# generic_RGB_LED_driver.net
KiCad netlist of a schematic drawn in EAGLE
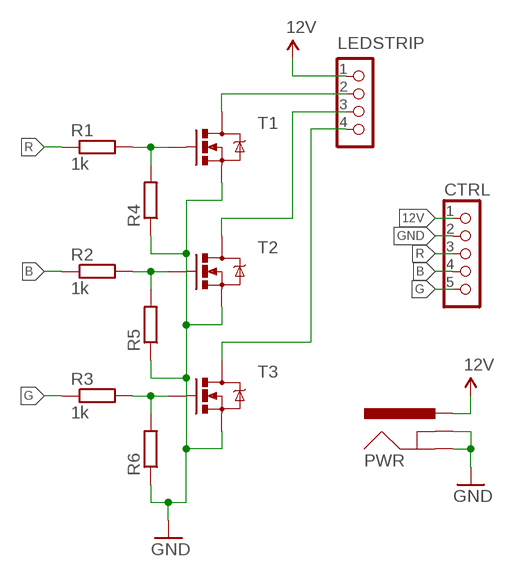
[diagram p0: schematic, sheet 1]

(export (version "E")
  (design (tool "Eeschema 10.0.6"))
  (components
    (comp (ref "CTRL")
      (value "CON_HEADER_1X05-PTH")
      (footprint "eagle-import:M1X5")
      (libsource (lib "eagle-import") (part "CON_HEADER_1X05-PTH"))
    )
    (comp (ref "LEDSTRIP")
      (value "12vBRG")
      (footprint "eagle-import:M1X4")
      (libsource (lib "eagle-import") (part "CON_HEADER_1X04"))
    )
    (comp (ref "PWR")
      (value "POWER_JACKPTH")
      (footprint "eagle-import:POWER_JACK_PTH")
      (libsource (lib "eagle-import") (part "POWER_JACKPTH"))
    )
    (comp (ref "R1")
      (value "1k")
      (footprint "eagle-import:R603")
      (libsource (lib "eagle-import") (part "RESISTOR-0603"))
    )
    (comp (ref "R2")
      (value "1k")
      (footprint "eagle-import:R603")
      (libsource (lib "eagle-import") (part "RESISTOR-0603"))
    )
    (comp (ref "R3")
      (value "1k")
      (footprint "eagle-import:R603")
      (libsource (lib "eagle-import") (part "RESISTOR-0603"))
    )
    (comp (ref "R4")
      (value "RESISTOR-0603")
      (footprint "eagle-import:R603")
      (libsource (lib "eagle-import") (part "RESISTOR-0603"))
    )
    (comp (ref "R5")
      (value "RESISTOR-0603")
      (footprint "eagle-import:R603")
      (libsource (lib "eagle-import") (part "RESISTOR-0603"))
    )
    (comp (ref "R6")
      (value "RESISTOR-0603")
      (footprint "eagle-import:R603")
      (libsource (lib "eagle-import") (part "RESISTOR-0603"))
    )
    (comp (ref "T1")
      (value "MOSFET-NCHANNELFDD8780")
      (footprint "eagle-import:DPAK")
      (libsource (lib "eagle-import") (part "MOSFET-NCHANNELFDD8780"))
    )
    (comp (ref "T2")
      (value "MOSFET-NCHANNELFDD8780")
      (footprint "eagle-import:DPAK")
      (libsource (lib "eagle-import") (part "MOSFET-NCHANNELFDD8780"))
    )
    (comp (ref "T3")
      (value "MOSFET-NCHANNELFDD8780")
      (footprint "eagle-import:DPAK")
      (libsource (lib "eagle-import") (part "MOSFET-NCHANNELFDD8780"))
    )
  )
  (nets
    (net (code "1") (name "12V") (class "Default")
      (node (ref "CTRL") (pin "1") (pinfunction "1_1") (pintype "bidirectional"))
      (node (ref "LEDSTRIP") (pin "1") (pinfunction "1_1") (pintype "bidirectional"))
      (node (ref "PWR") (pin "PWR") (pinfunction "PWR_PWR") (pintype "bidirectional"))
    )
    (net (code "2") (name "B") (class "Default")
      (node (ref "CTRL") (pin "4") (pinfunction "4_4") (pintype "bidirectional"))
      (node (ref "R2") (pin "1") (pinfunction "1_1") (pintype "passive"))
    )
    (net (code "3") (name "G") (class "Default")
      (node (ref "CTRL") (pin "5") (pinfunction "5_5") (pintype "bidirectional"))
      (node (ref "R3") (pin "1") (pinfunction "1_1") (pintype "passive"))
    )
    (net (code "4") (name "GND") (class "Default")
      (node (ref "CTRL") (pin "2") (pinfunction "2_2") (pintype "bidirectional"))
      (node (ref "PWR") (pin "GND") (pinfunction "GND_GND") (pintype "bidirectional"))
      (node (ref "PWR") (pin "GNDBREAK") (pinfunction "GNDBREAK_GNDBREAK") (pintype "bidirectional"))
      (node (ref "R4") (pin "1") (pinfunction "1_1") (pintype "passive"))
      (node (ref "R5") (pin "1") (pinfunction "1_1") (pintype "passive"))
      (node (ref "R6") (pin "1") (pinfunction "1_1") (pintype "passive"))
      (node (ref "T1") (pin "3") (pinfunction "S_3") (pintype "passive"))
      (node (ref "T2") (pin "3") (pinfunction "S_3") (pintype "passive"))
      (node (ref "T3") (pin "3") (pinfunction "S_3") (pintype "passive"))
    )
    (net (code "5") (name "Net-(T1-D)") (class "Default")
      (node (ref "LEDSTRIP") (pin "2") (pinfunction "2_2") (pintype "bidirectional"))
      (node (ref "T1") (pin "4") (pinfunction "D_4") (pintype "passive"))
    )
    (net (code "6") (name "Net-(T1-G)") (class "Default")
      (node (ref "R1") (pin "2") (pinfunction "2_2") (pintype "passive"))
      (node (ref "R4") (pin "2") (pinfunction "2_2") (pintype "passive"))
      (node (ref "T1") (pin "1") (pinfunction "G_1") (pintype "passive"))
    )
    (net (code "7") (name "Net-(T2-D)") (class "Default")
      (node (ref "LEDSTRIP") (pin "3") (pinfunction "3_3") (pintype "bidirectional"))
      (node (ref "T2") (pin "4") (pinfunction "D_4") (pintype "passive"))
    )
    (net (code "8") (name "Net-(T2-G)") (class "Default")
      (node (ref "R2") (pin "2") (pinfunction "2_2") (pintype "passive"))
      (node (ref "R5") (pin "2") (pinfunction "2_2") (pintype "passive"))
      (node (ref "T2") (pin "1") (pinfunction "G_1") (pintype "passive"))
    )
    (net (code "9") (name "Net-(T3-D)") (class "Default")
      (node (ref "LEDSTRIP") (pin "4") (pinfunction "4_4") (pintype "bidirectional"))
      (node (ref "T3") (pin "4") (pinfunction "D_4") (pintype "passive"))
    )
    (net (code "10") (name "Net-(T3-G)") (class "Default")
      (node (ref "R3") (pin "2") (pinfunction "2_2") (pintype "passive"))
      (node (ref "R6") (pin "2") (pinfunction "2_2") (pintype "passive"))
      (node (ref "T3") (pin "1") (pinfunction "G_1") (pintype "passive"))
    )
    (net (code "11") (name "R") (class "Default")
      (node (ref "CTRL") (pin "3") (pinfunction "3_3") (pintype "bidirectional"))
      (node (ref "R1") (pin "1") (pinfunction "1_1") (pintype "passive"))
    )
  )
)
